# lightmagic.net
KiCad netlist of a schematic drawn in EAGLE
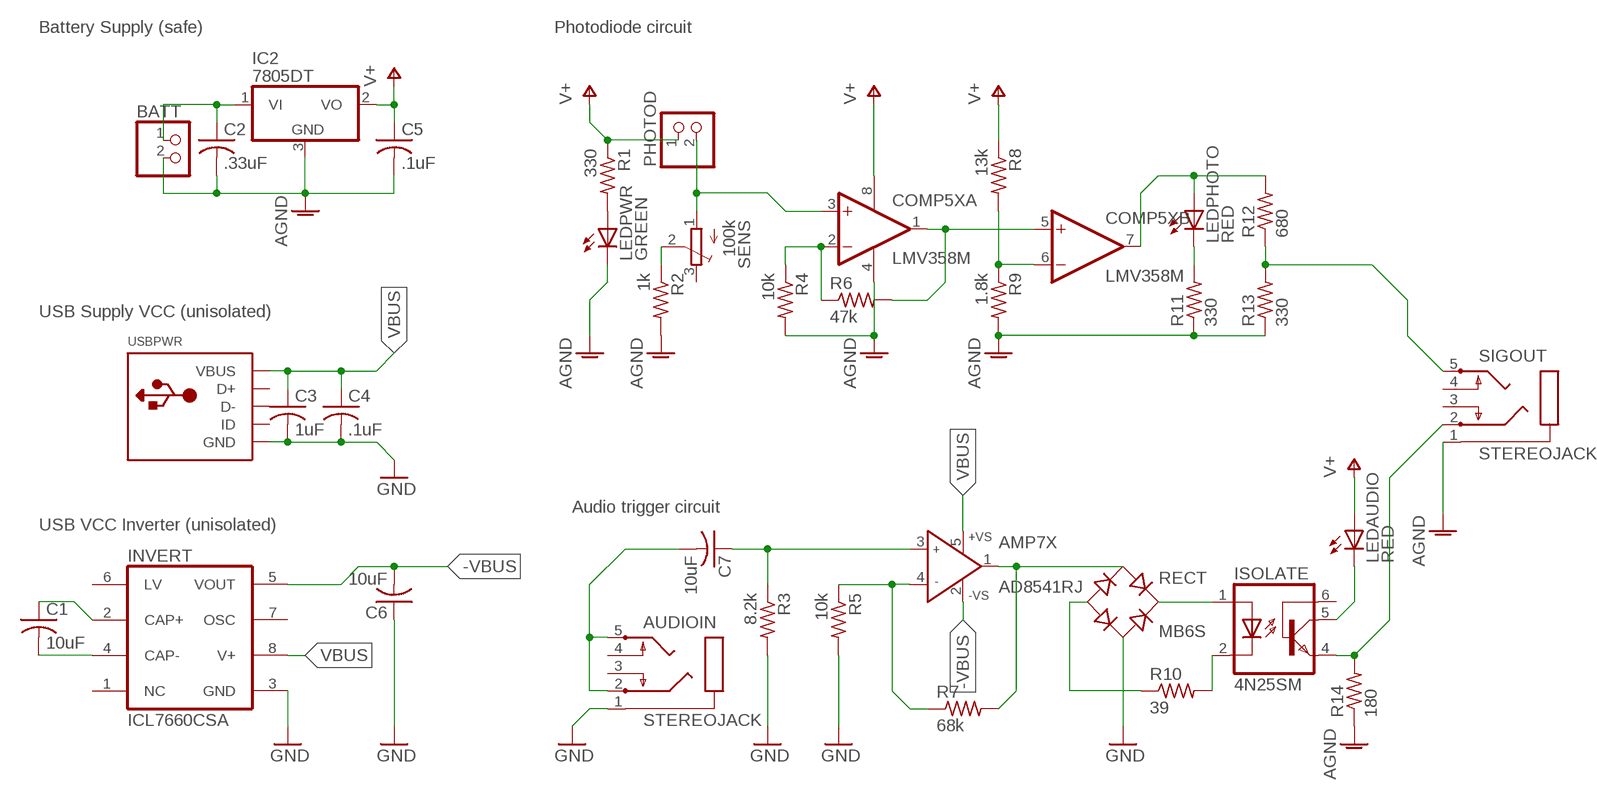
[diagram p0: schematic, sheet 1]

(export (version "E")
  (design (tool "Eeschema 10.0.6"))
  (components
    (comp (ref "AMP7X")
      (value "AD8541RJ")
      (footprint "eagle-import:SOT23-5")
      (fields
        (field (name "MF") "ALTERA CORPORATION")
        (field (name "MPN") "AD8541ARTZ-REEL7")
        (field (name "MPN_1") "AD8541ARTZ-R2")
        (field (name "OC_NEWARK") "28X4209")
      )
      (libsource (lib "eagle-import") (part "AD8541RJ"))
    )
    (comp (ref "AUDIOIN")
      (value "STEREOJACK")
      (footprint "eagle-import:STX3100")
      (fields (field (name "MF") "SWITCHCRAFT") (field (name "MPN") "35RAPC4BHN2"))
      (libsource (lib "eagle-import") (part "STEREOJACK"))
    )
    (comp (ref "BATT")
      (value "PINHD-1X2")
      (footprint "eagle-import:1X02")
      (fields (field (name "MF") "TYCO ELECTRONICS") (field (name "MPN") "640456-2"))
      (libsource (lib "eagle-import") (part "PINHD-1X2"))
    )
    (comp (ref "C1")
      (value "10uF")
      (footprint "eagle-import:C0805")
      (fields (field (name "MPN") "GRT21BR61E106KE13L"))
      (libsource (lib "eagle-import") (part "C-USC0805"))
    )
    (comp (ref "C2")
      (value ".33uF")
      (footprint "eagle-import:C0805")
      (fields (field (name "MPN") "MC0805B334K500CT"))
      (libsource (lib "eagle-import") (part "C-USC0805"))
    )
    (comp (ref "C3")
      (value "1uF")
      (footprint "eagle-import:C0805")
      (fields (field (name "MPN") "C0805X104K3RAC3316"))
      (libsource (lib "eagle-import") (part "C-USC0805"))
    )
    (comp (ref "C4")
      (value ".1uF")
      (footprint "eagle-import:C0805")
      (fields (field (name "MPN") "0805YC104KAT2A"))
      (libsource (lib "eagle-import") (part "C-USC0805"))
    )
    (comp (ref "C5")
      (value ".1uF")
      (footprint "eagle-import:C0805")
      (fields (field (name "MPN") "0805YC104KAT2A"))
      (libsource (lib "eagle-import") (part "C-USC0805"))
    )
    (comp (ref "C6")
      (value "10uF")
      (footprint "eagle-import:C0805")
      (fields (field (name "MPN") "GRT21BR61E106KE13L"))
      (libsource (lib "eagle-import") (part "C-USC0805"))
    )
    (comp (ref "C7")
      (value "10uF")
      (footprint "eagle-import:C0805")
      (fields (field (name "MPN") "GRT21BR61E106KE13L"))
      (libsource (lib "eagle-import") (part "C-USC0805"))
    )
    (comp (ref "COMP5X")
      (value "LMV358M")
      (footprint "eagle-import:SO08")
      (fields (field (name "MPN") "LMV358M") (field (name "OC_NEWARK") "97K3153"))
      (libsource (lib "eagle-import") (part "LMV358?M"))
    )
    (comp (ref "IC2")
      (value "7805DT")
      (footprint "eagle-import:TO252")
      (fields (field (name "MF") "ON SEMICONDUCTOR") (field (name "MPN") "MC7805CDTG"))
      (libsource (lib "eagle-import") (part "78DT05"))
    )
    (comp (ref "INVERT")
      (value "ICL7660CSA")
      (footprint "eagle-import:SO08")
      (fields
        (field (name "MF") "MAXIM")
        (field (name "MF_1") "NATIONAL SEMICONDUCTOR")
        (field (name "MPN") "LMC7660IM/NOPB")
        (field (name "OC_NEWARK") "41K2738")
      )
      (libsource (lib "eagle-import") (part "ICL7660CSA"))
    )
    (comp (ref "ISOLATE")
      (value "4N25SM")
      (footprint "eagle-import:DIL6-SMD")
      (fields
        (field (name "MF") "FAIRCHILD SEMICONDUCTOR")
        (field (name "MPN") "4N25-300E")
        (field (name "OC_NEWARK") "13M5766")
      )
      (libsource (lib "eagle-import") (part "4N?MS25"))
    )
    (comp (ref "LEDAUDIO")
      (value "RED")
      (footprint "eagle-import:CHIP-LED0805")
      (fields (field (name "MPN") "QTLP630C7TR"))
      (libsource (lib "eagle-import") (part "LEDCHIP-LED0805"))
    )
    (comp (ref "LEDPHOTO")
      (value "RED")
      (footprint "eagle-import:CHIP-LED0805")
      (fields (field (name "MPN") "QTLP630C7TR"))
      (libsource (lib "eagle-import") (part "LEDCHIP-LED0805"))
    )
    (comp (ref "LEDPWR")
      (value "GREEN")
      (footprint "eagle-import:CHIP-LED0805")
      (fields (field (name "MPN") "QTLP630C7TR"))
      (libsource (lib "eagle-import") (part "LEDCHIP-LED0805"))
    )
    (comp (ref "PHOTOD")
      (value "PINHD-1X2")
      (footprint "eagle-import:1X02")
      (fields (field (name "MF") "TYCO ELECTRONICS") (field (name "MPN") "640456-2"))
      (libsource (lib "eagle-import") (part "PINHD-1X2"))
    )
    (comp (ref "R1")
      (value "330")
      (footprint "eagle-import:R0805")
      (fields (field (name "MPN") "ERJ-6ENF3300V"))
      (libsource (lib "eagle-import") (part "R-US_R0805"))
    )
    (comp (ref "R2")
      (value "1k")
      (footprint "eagle-import:R0805")
      (fields (field (name "MPN") "ERJ-6ENF12R0V"))
      (libsource (lib "eagle-import") (part "R-US_R0805"))
    )
    (comp (ref "R3")
      (value "8.2k")
      (footprint "eagle-import:R0805")
      (fields (field (name "MF") "Multicomp Passives") (field (name "MPN") "MC01W080518K2"))
      (libsource (lib "eagle-import") (part "R-US_R0805"))
    )
    (comp (ref "R4")
      (value "10k")
      (footprint "eagle-import:R0805")
      (fields (field (name "MF") "VISHAY/DALE") (field (name "MPN") "CRCW080510K0FKTA"))
      (libsource (lib "eagle-import") (part "R-US_R0805"))
    )
    (comp (ref "R5")
      (value "10k")
      (footprint "eagle-import:R0805")
      (fields (field (name "MF") "VISHAY/DALE") (field (name "MPN") "CRCW080510K0FKTA"))
      (libsource (lib "eagle-import") (part "R-US_R0805"))
    )
    (comp (ref "R6")
      (value "47k")
      (footprint "eagle-import:R0805")
      (fields (field (name "MF") "VISHAY/DALE") (field (name "MPN") "CRCW080547K0FKEA"))
      (libsource (lib "eagle-import") (part "R-US_R0805"))
    )
    (comp (ref "R7")
      (value "68k")
      (footprint "eagle-import:R0805")
      (fields (field (name "MF") "VISHAY/DALE") (field (name "MPN") "CRCW080568K0FKEA"))
      (libsource (lib "eagle-import") (part "R-US_R0805"))
    )
    (comp (ref "R8")
      (value "13k")
      (footprint "eagle-import:R0805")
      (fields (field (name "MF") "VISHAY/DALE") (field (name "MPN") "CRCW080513K0FKEA"))
      (libsource (lib "eagle-import") (part "R-US_R0805"))
    )
    (comp (ref "R9")
      (value "1.8k")
      (footprint "eagle-import:R0805")
      (fields (field (name "MF") "VISHAY/DALE") (field (name "MPN") "CRCW08051K80FKEA"))
      (libsource (lib "eagle-import") (part "R-US_R0805"))
    )
    (comp (ref "R10")
      (value "39")
      (footprint "eagle-import:R0805")
      (fields (field (name "MPN") "ERJ-6GEYJ390V"))
      (libsource (lib "eagle-import") (part "R-US_R0805"))
    )
    (comp (ref "R11")
      (value "330")
      (footprint "eagle-import:R0805")
      (fields (field (name "MPN") "ERJ-6ENF3300V"))
      (libsource (lib "eagle-import") (part "R-US_R0805"))
    )
    (comp (ref "R12")
      (value "680")
      (footprint "eagle-import:R0805")
      (fields (field (name "MPN") "ERA-6AEB681V"))
      (libsource (lib "eagle-import") (part "R-US_R0805"))
    )
    (comp (ref "R13")
      (value "330")
      (footprint "eagle-import:R0805")
      (fields (field (name "MPN") "ERJ-6ENF3300V"))
      (libsource (lib "eagle-import") (part "R-US_R0805"))
    )
    (comp (ref "R14")
      (value "180")
      (footprint "eagle-import:R0805")
      (fields (field (name "MF") "VISHAY/DALE") (field (name "MPN") "CRCW0805180RJNEA"))
      (libsource (lib "eagle-import") (part "R-US_R0805"))
    )
    (comp (ref "RECT")
      (value "MB6S")
      (footprint "eagle-import:SOIC-4")
      (fields (field (name "MF") "FAIRCHILD SEMICONDUCTOR"))
      (libsource (lib "eagle-import") (part "MBS6"))
    )
    (comp (ref "SENS")
      (value "100k")
      (footprint "eagle-import:TC33X")
      (fields (field (name "MPN") "CRCW0805100KJNEA"))
      (libsource (lib "eagle-import") (part "TRIMPOTTC33X"))
    )
    (comp (ref "SIGOUT")
      (value "STEREOJACK")
      (footprint "eagle-import:STX3100")
      (fields (field (name "MF") "SWITCHCRAFT") (field (name "MPN") "35RAPC4BHN2"))
      (libsource (lib "eagle-import") (part "STEREOJACK"))
    )
    (comp (ref "USBPWR")
      (value "USBMINIB")
      (footprint "eagle-import:USB-MINIB")
      (fields (field (name "MPN") "1734035-1"))
      (libsource (lib "eagle-import") (part "USBMINIB"))
    )
  )
  (nets
    (net (code "1") (name "-VBUS") (class "Default")
      (node (ref "AMP7X") (pin "2") (pinfunction "-VS_2") (pintype "input"))
      (node (ref "C6") (pin "2") (pinfunction "2_2") (pintype "passive"))
      (node (ref "INVERT") (pin "5") (pinfunction "VOUT_5") (pintype "output"))
    )
    (net (code "2") (name "AGND") (class "Default")
      (node (ref "BATT") (pin "2") (pinfunction "2_2") (pintype "passive"))
      (node (ref "C2") (pin "2") (pinfunction "2_2") (pintype "passive"))
      (node (ref "C5") (pin "2") (pinfunction "2_2") (pintype "passive"))
      (node (ref "COMP5X") (pin "4") (pinfunction "V-_4") (pintype "power_in"))
      (node (ref "IC2") (pin "3") (pinfunction "GND_3") (pintype "passive"))
      (node (ref "LEDPWR") (pin "C") (pinfunction "C_C") (pintype "passive"))
      (node (ref "R11") (pin "1") (pinfunction "1_1") (pintype "passive"))
      (node (ref "R13") (pin "1") (pinfunction "1_1") (pintype "passive"))
      (node (ref "R14") (pin "1") (pinfunction "1_1") (pintype "passive"))
      (node (ref "R2") (pin "2") (pinfunction "2_2") (pintype "passive"))
      (node (ref "R4") (pin "2") (pinfunction "2_2") (pintype "passive"))
      (node (ref "R9") (pin "2") (pinfunction "2_2") (pintype "passive"))
      (node (ref "SIGOUT") (pin "1") (pinfunction "1_1") (pintype "passive"))
    )
    (net (code "3") (name "GND") (class "Default")
      (node (ref "AUDIOIN") (pin "1") (pinfunction "1_1") (pintype "passive"))
      (node (ref "C3") (pin "2") (pinfunction "2_2") (pintype "passive"))
      (node (ref "C4") (pin "2") (pinfunction "2_2") (pintype "passive"))
      (node (ref "C6") (pin "1") (pinfunction "1_1") (pintype "passive"))
      (node (ref "INVERT") (pin "3") (pinfunction "GND_3") (pintype "power_in"))
      (node (ref "R3") (pin "2") (pinfunction "2_2") (pintype "passive"))
      (node (ref "R5") (pin "2") (pinfunction "2_2") (pintype "passive"))
      (node (ref "RECT") (pin "~2") (pinfunction "AC2_~2") (pintype "passive"))
      (node (ref "USBPWR") (pin "GND") (pinfunction "GND_GND") (pintype "power_in"))
    )
    (net (code "4") (name "Net-(AMP7X-IN+)") (class "Default")
      (node (ref "AMP7X") (pin "3") (pinfunction "IN+_3") (pintype "input"))
      (node (ref "C7") (pin "1") (pinfunction "1_1") (pintype "passive"))
      (node (ref "R3") (pin "1") (pinfunction "1_1") (pintype "passive"))
    )
    (net (code "5") (name "Net-(AMP7X-IN-)") (class "Default")
      (node (ref "AMP7X") (pin "4") (pinfunction "IN-_4") (pintype "input"))
      (node (ref "R5") (pin "1") (pinfunction "1_1") (pintype "passive"))
      (node (ref "R7") (pin "1") (pinfunction "1_1") (pintype "passive"))
    )
    (net (code "6") (name "Net-(AMP7X-OUT)") (class "Default")
      (node (ref "AMP7X") (pin "1") (pinfunction "OUT_1") (pintype "output"))
      (node (ref "R7") (pin "2") (pinfunction "2_2") (pintype "passive"))
      (node (ref "RECT") (pin "~1") (pinfunction "AC1_~1") (pintype "passive"))
    )
    (net (code "7") (name "Net-(AUDIOIN-Pad2)") (class "Default")
      (node (ref "AUDIOIN") (pin "2") (pinfunction "2_2") (pintype "passive"))
      (node (ref "AUDIOIN") (pin "5") (pinfunction "5_5") (pintype "passive"))
      (node (ref "C7") (pin "2") (pinfunction "2_2") (pintype "passive"))
    )
    (net (code "8") (name "Net-(COMP5XA-+IN)") (class "Default")
      (node (ref "COMP5X") (pin "3") (pinfunction "+IN_3") (pintype "input"))
      (node (ref "PHOTOD") (pin "2") (pinfunction "2_2") (pintype "passive"))
      (node (ref "SENS") (pin "1") (pinfunction "A_1") (pintype "passive"))
    )
    (net (code "9") (name "Net-(COMP5XA--IN)") (class "Default")
      (node (ref "COMP5X") (pin "2") (pinfunction "-IN_2") (pintype "input"))
      (node (ref "R4") (pin "1") (pinfunction "1_1") (pintype "passive"))
      (node (ref "R6") (pin "1") (pinfunction "1_1") (pintype "passive"))
    )
    (net (code "10") (name "Net-(COMP5XA-OUT)") (class "Default")
      (node (ref "COMP5X") (pin "1") (pinfunction "OUT_1") (pintype "output"))
      (node (ref "COMP5X") (pin "5") (pinfunction "+IN_5") (pintype "input"))
      (node (ref "R6") (pin "2") (pinfunction "2_2") (pintype "passive"))
    )
    (net (code "11") (name "Net-(COMP5XB--IN)") (class "Default")
      (node (ref "COMP5X") (pin "6") (pinfunction "-IN_6") (pintype "input"))
      (node (ref "R8") (pin "2") (pinfunction "2_2") (pintype "passive"))
      (node (ref "R9") (pin "1") (pinfunction "1_1") (pintype "passive"))
    )
    (net (code "12") (name "Net-(COMP5XB-OUT)") (class "Default")
      (node (ref "COMP5X") (pin "7") (pinfunction "OUT_7") (pintype "output"))
      (node (ref "LEDPHOTO") (pin "A") (pinfunction "A_A") (pintype "passive"))
      (node (ref "R12") (pin "2") (pinfunction "2_2") (pintype "passive"))
    )
    (net (code "13") (name "Net-(IC2-VI)") (class "Default")
      (node (ref "BATT") (pin "1") (pinfunction "1_1") (pintype "passive"))
      (node (ref "C2") (pin "1") (pinfunction "1_1") (pintype "passive"))
      (node (ref "IC2") (pin "1") (pinfunction "VI_1") (pintype "input"))
    )
    (net (code "14") (name "Net-(INVERT-CAP+)") (class "Default")
      (node (ref "C1") (pin "1") (pinfunction "1_1") (pintype "passive"))
      (node (ref "INVERT") (pin "2") (pinfunction "CAP+_2") (pintype "passive"))
    )
    (net (code "15") (name "Net-(INVERT-CAP-)") (class "Default")
      (node (ref "C1") (pin "2") (pinfunction "2_2") (pintype "passive"))
      (node (ref "INVERT") (pin "4") (pinfunction "CAP-_4") (pintype "passive"))
    )
    (net (code "16") (name "Net-(ISOLATE-A)") (class "Default")
      (node (ref "ISOLATE") (pin "1") (pinfunction "A_1") (pintype "passive"))
      (node (ref "RECT") (pin "+") (pinfunction "+_+") (pintype "passive"))
    )
    (net (code "17") (name "Net-(ISOLATE-C)") (class "Default")
      (node (ref "ISOLATE") (pin "2") (pinfunction "C_2") (pintype "passive"))
      (node (ref "R10") (pin "2") (pinfunction "2_2") (pintype "passive"))
    )
    (net (code "18") (name "Net-(ISOLATE-COL)") (class "Default")
      (node (ref "ISOLATE") (pin "5") (pinfunction "COL_5") (pintype "passive"))
      (node (ref "LEDAUDIO") (pin "C") (pinfunction "C_C") (pintype "passive"))
    )
    (net (code "19") (name "Net-(ISOLATE-EMI)") (class "Default")
      (node (ref "ISOLATE") (pin "4") (pinfunction "EMI_4") (pintype "passive"))
      (node (ref "R14") (pin "2") (pinfunction "2_2") (pintype "passive"))
      (node (ref "SIGOUT") (pin "2") (pinfunction "2_2") (pintype "passive"))
    )
    (net (code "20") (name "Net-(LEDPHOTO-PadC)") (class "Default")
      (node (ref "LEDPHOTO") (pin "C") (pinfunction "C_C") (pintype "passive"))
      (node (ref "R11") (pin "2") (pinfunction "2_2") (pintype "passive"))
    )
    (net (code "21") (name "Net-(LEDPWR-PadA)") (class "Default")
      (node (ref "LEDPWR") (pin "A") (pinfunction "A_A") (pintype "passive"))
      (node (ref "R1") (pin "2") (pinfunction "2_2") (pintype "passive"))
    )
    (net (code "22") (name "Net-(R10-Pad1)") (class "Default")
      (node (ref "R10") (pin "1") (pinfunction "1_1") (pintype "passive"))
      (node (ref "RECT") (pin "-") (pinfunction "-_-") (pintype "passive"))
    )
    (net (code "23") (name "Net-(R12-Pad1)") (class "Default")
      (node (ref "R12") (pin "1") (pinfunction "1_1") (pintype "passive"))
      (node (ref "R13") (pin "2") (pinfunction "2_2") (pintype "passive"))
      (node (ref "SIGOUT") (pin "5") (pinfunction "5_5") (pintype "passive"))
    )
    (net (code "24") (name "Net-(SENS-S)") (class "Default")
      (node (ref "R2") (pin "1") (pinfunction "1_1") (pintype "passive"))
      (node (ref "SENS") (pin "2") (pinfunction "S_2") (pintype "passive"))
    )
    (net (code "25") (name "V+") (class "Default")
      (node (ref "C5") (pin "1") (pinfunction "1_1") (pintype "passive"))
      (node (ref "COMP5X") (pin "8") (pinfunction "V+_8") (pintype "power_in"))
      (node (ref "IC2") (pin "2") (pinfunction "VO_2") (pintype "passive"))
      (node (ref "LEDAUDIO") (pin "A") (pinfunction "A_A") (pintype "passive"))
      (node (ref "PHOTOD") (pin "1") (pinfunction "1_1") (pintype "passive"))
      (node (ref "R1") (pin "1") (pinfunction "1_1") (pintype "passive"))
      (node (ref "R8") (pin "1") (pinfunction "1_1") (pintype "passive"))
    )
    (net (code "26") (name "VBUS") (class "Default")
      (node (ref "AMP7X") (pin "5") (pinfunction "+VS_5") (pintype "input"))
      (node (ref "C3") (pin "1") (pinfunction "1_1") (pintype "passive"))
      (node (ref "C4") (pin "1") (pinfunction "1_1") (pintype "passive"))
      (node (ref "INVERT") (pin "8") (pinfunction "V+_8") (pintype "power_in"))
      (node (ref "USBPWR") (pin "VBUS") (pinfunction "VBUS_VBUS") (pintype "power_in"))
    )
    (net (code "27") (name "unconnected-(AUDIOIN-Pad3)") (class "Default")
      (node (ref "AUDIOIN") (pin "3") (pinfunction "3_3") (pintype "passive"))
    )
    (net (code "28") (name "unconnected-(AUDIOIN-Pad4)") (class "Default")
      (node (ref "AUDIOIN") (pin "4") (pinfunction "4_4") (pintype "passive"))
    )
    (net (code "29") (name "unconnected-(INVERT-LV-Pad6)") (class "Default")
      (node (ref "INVERT") (pin "6") (pinfunction "LV_6") (pintype "passive"))
    )
    (net (code "30") (name "unconnected-(INVERT-NC-Pad1)") (class "Default")
      (node (ref "INVERT") (pin "1") (pinfunction "NC_1") (pintype "no_connect"))
    )
    (net (code "31") (name "unconnected-(INVERT-OSC-Pad7)") (class "Default")
      (node (ref "INVERT") (pin "7") (pinfunction "OSC_7") (pintype "output"))
    )
    (net (code "32") (name "unconnected-(ISOLATE-BAS-Pad6)") (class "Default")
      (node (ref "ISOLATE") (pin "6") (pinfunction "BAS_6") (pintype "passive"))
    )
    (net (code "33") (name "unconnected-(SENS-E-Pad3)") (class "Default")
      (node (ref "SENS") (pin "3") (pinfunction "E_3") (pintype "passive"))
    )
    (net (code "34") (name "unconnected-(SIGOUT-Pad3)") (class "Default")
      (node (ref "SIGOUT") (pin "3") (pinfunction "3_3") (pintype "passive"))
    )
    (net (code "35") (name "unconnected-(SIGOUT-Pad4)") (class "Default")
      (node (ref "SIGOUT") (pin "4") (pinfunction "4_4") (pintype "passive"))
    )
    (net (code "36") (name "unconnected-(USBPWR-PadD+)") (class "Default")
      (node (ref "USBPWR") (pin "D+") (pinfunction "D+_D+") (pintype "bidirectional"))
    )
    (net (code "37") (name "unconnected-(USBPWR-PadD-)") (class "Default")
      (node (ref "USBPWR") (pin "D-") (pinfunction "D-_D-") (pintype "bidirectional"))
    )
    (net (code "38") (name "unconnected-(USBPWR-PadID)") (class "Default")
      (node (ref "USBPWR") (pin "ID") (pinfunction "ID_ID") (pintype "bidirectional"))
    )
  )
)
